# top_blank.net
KiCad netlist of a schematic drawn in Altium Designer
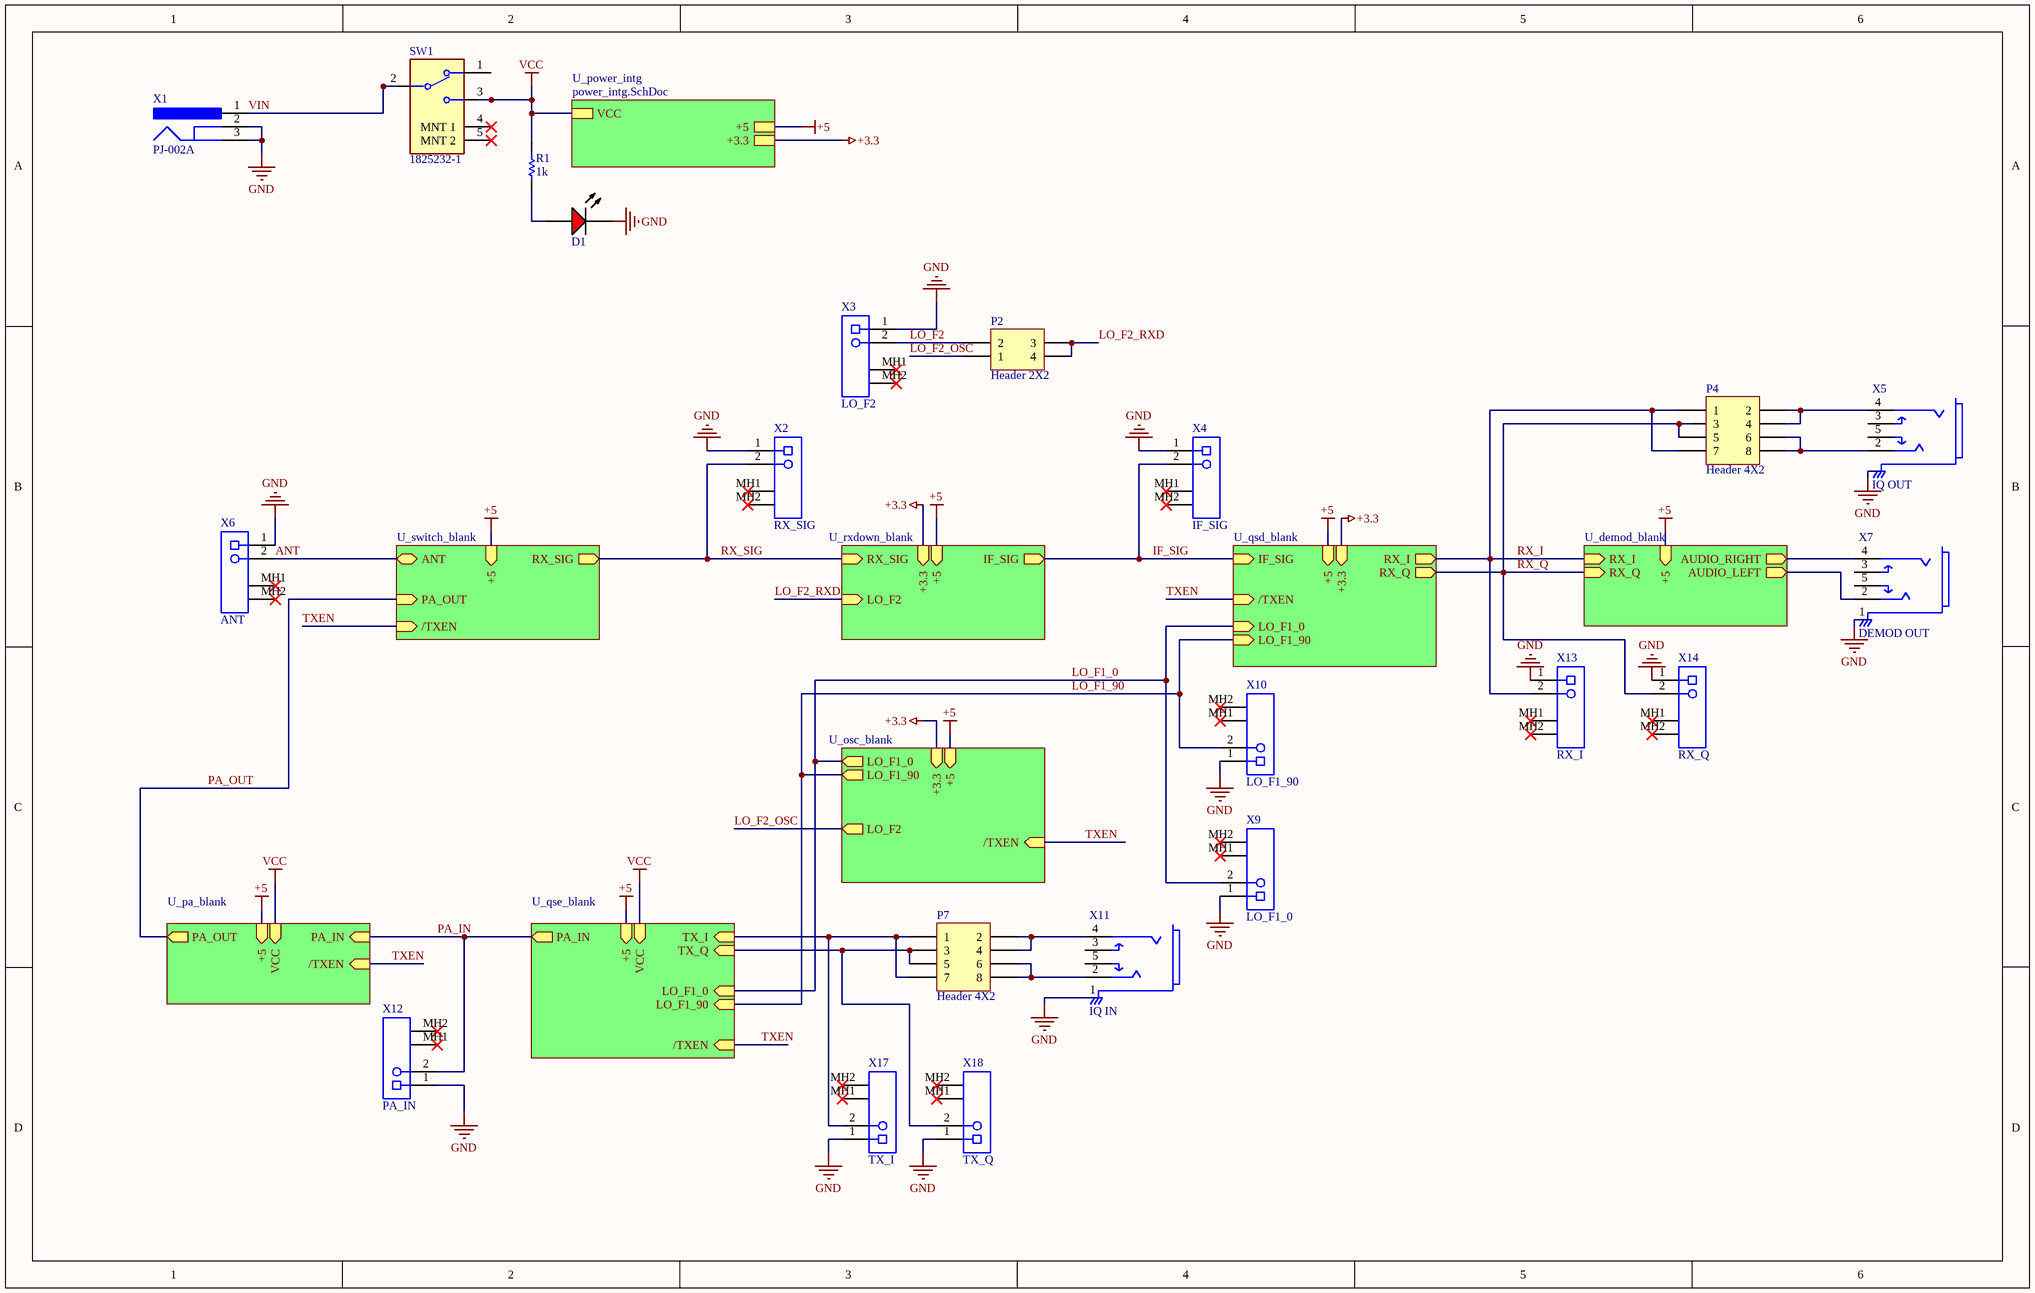
[diagram p0: top_blank.SchDoc]

(export (version "E")
  (design (tool "Eeschema 10.0.6"))
  (components
    (comp (ref "D1")
      (value "HLMP-3301")
      (footprint "AVAG-HLMP-3301-2")
      (description "T-1 3/4 (5 mm) Diffused LED Lamp, 1.9 V, -40 to 100 degC, 2-Pin THD, RoHS, Bulk")
      (fields (field (name "MANUFACTURER") "Avago"))
      (libsource (lib "Altium Content Vault") (part "LED-RED-K1A2-2"))
    )
    (comp (ref "P2")
      (value "Header 2X2")
      (footprint "HDR2X2")
      (description "Header, 2-Pin, Dual row")
      (fields (field (name "PUBLISHER") "Altium Limited"))
      (libsource (lib "Miscellaneous Connectors") (part "Header 2X2"))
    )
    (comp (ref "P4")
      (value "Header 4X2")
      (footprint "HDR2X4")
      (description "Header, 4-Pin, Dual row")
      (fields (field (name "PUBLISHER") "Altium Limited"))
      (libsource (lib "Miscellaneous Connectors") (part "Header 4X2"))
    )
    (comp (ref "P7")
      (value "Header 4X2")
      (footprint "HDR2X4")
      (description "Header, 4-Pin, Dual row")
      (fields (field (name "PUBLISHER") "Altium Limited"))
      (libsource (lib "Miscellaneous Connectors") (part "Header 4X2"))
    )
    (comp (ref "R1")
      (value "1k")
      (footprint "AXIAL-0.4")
      (description "Resistor")
      (fields (field (name "Comment") "Res1") (field (name "PUBLISHER") "Altium Limited"))
      (libsource (lib "Miscellaneous Devices") (part "Res1"))
    )
    (comp (ref "SW1")
      (value "1825232-1")
      (footprint "FP-1825232-1-MFG")
      (description "SWITCH SLIDE SPDT 200MA 30V")
      (fields
        (field (name "OCTOPART") "https://octopart.com/1825232-1-te+connectivity-45209882")
        (field (name "MANUFACTURER") "TE Connectivity")
      )
      (libsource (lib "Altium Content Vault") (part "b81b21e7de6c425a317152e587b8097"))
    )
    (comp (ref "X1")
      (value "PJ-002A")
      (footprint "CUI-PJ-002A_V")
      (fields (field (name "MANUFACTURER") "CUIInc."))
      (libsource (lib "Altium Content Vault") (part "JACK-2CD3-RN"))
    )
    (comp (ref "X2")
      (value "RX_SIG")
      (footprint "TECO-1-1337543-0_V")
      (fields (field (name "MANUFACTURER") "TE Connectivity"))
      (libsource (lib "Altium Content Vault") (part "CN-1P-F-R2_A"))
    )
    (comp (ref "X3")
      (value "LO_F2")
      (footprint "TECO-1-1337543-0_V")
      (fields (field (name "MANUFACTURER") "TE Connectivity"))
      (libsource (lib "") (part "CN-1P-F-R2_A_2"))
    )
    (comp (ref "X4")
      (value "IF_SIG")
      (footprint "TECO-1-1337543-0_V")
      (fields (field (name "MANUFACTURER") "TE Connectivity"))
      (libsource (lib "Altium Content Vault") (part "CN-1P-F-R2_A"))
    )
    (comp (ref "X5")
      (value "IQ OUT")
      (footprint "FP-35RAPC4BV4-MFG")
      (description "CONN JACK STEREO 3.5MM R/A")
      (fields (field (name "MANUFACTURER") "Switchcraft") (field (name "OBSOLETE PART") "true"))
      (libsource (lib "Altium Content Vault") (part "75ff47c9dea01840d0d9527457fc737"))
    )
    (comp (ref "X6")
      (value "ANT")
      (footprint "TECO-1-1337543-0_V")
      (fields (field (name "MANUFACTURER") "TE Connectivity"))
      (libsource (lib "") (part "CN-1P-F-R2_A_2"))
    )
    (comp (ref "X7")
      (value "DEMOD OUT")
      (footprint "FP-35RAPC4BV4-MFG")
      (description "CONN JACK STEREO 3.5MM R/A")
      (fields (field (name "MANUFACTURER") "Switchcraft") (field (name "OBSOLETE PART") "true"))
      (libsource (lib "Altium Content Vault") (part "75ff47c9dea01840d0d9527457fc737"))
    )
    (comp (ref "X9")
      (value "LO_F1_0")
      (footprint "TECO-1-1337543-0_V")
      (fields (field (name "MANUFACTURER") "TE Connectivity"))
      (libsource (lib "") (part "CN-1P-F-R2_A_1"))
    )
    (comp (ref "X10")
      (value "LO_F1_90")
      (footprint "TECO-1-1337543-0_V")
      (fields (field (name "MANUFACTURER") "TE Connectivity"))
      (libsource (lib "") (part "CN-1P-F-R2_A_1"))
    )
    (comp (ref "X11")
      (value "IQ IN")
      (footprint "FP-35RAPC4BV4-MFG")
      (description "CONN JACK STEREO 3.5MM R/A")
      (fields (field (name "MANUFACTURER") "Switchcraft") (field (name "OBSOLETE PART") "true"))
      (libsource (lib "Altium Content Vault") (part "75ff47c9dea01840d0d9527457fc737"))
    )
    (comp (ref "X12")
      (value "PA_IN")
      (footprint "TECO-1-1337543-0_V")
      (fields (field (name "MANUFACTURER") "TE Connectivity"))
      (libsource (lib "") (part "CN-1P-F-R2_A_3"))
    )
    (comp (ref "X13")
      (value "RX_I")
      (footprint "TECO-1-1337543-0_V")
      (fields (field (name "MANUFACTURER") "TE Connectivity"))
      (libsource (lib "Altium Content Vault") (part "CN-1P-F-R2_A"))
    )
    (comp (ref "X14")
      (value "RX_Q")
      (footprint "TECO-1-1337543-0_V")
      (fields (field (name "MANUFACTURER") "TE Connectivity"))
      (libsource (lib "Altium Content Vault") (part "CN-1P-F-R2_A"))
    )
    (comp (ref "X17")
      (value "TX_I")
      (footprint "TECO-1-1337543-0_V")
      (fields (field (name "MANUFACTURER") "TE Connectivity"))
      (libsource (lib "") (part "CN-1P-F-R2_A_1"))
    )
    (comp (ref "X18")
      (value "TX_Q")
      (footprint "TECO-1-1337543-0_V")
      (fields (field (name "MANUFACTURER") "TE Connectivity"))
      (libsource (lib "") (part "CN-1P-F-R2_A_1"))
    )
  )
  (nets
    (net (code "3") (name "/ANT") (class "Default")
      (node (ref "X6") (pin "2") (pinfunction "2_2") (pintype "passive"))
    )
    (net (code "4") (name "/AUDIO_LEFT") (class "Default")
      (node (ref "X7") (pin "2") (pinfunction "2_2") (pintype "passive"))
    )
    (net (code "5") (name "/AUDIO_RIGHT") (class "Default")
      (node (ref "X7") (pin "4") (pinfunction "4_4") (pintype "passive"))
    )
    (net (code "6") (name "/IF_SIG") (class "Default")
      (node (ref "X4") (pin "2") (pinfunction "2_2") (pintype "passive"))
    )
    (net (code "7") (name "/LO_F1_0") (class "Default")
      (node (ref "X9") (pin "2") (pinfunction "2_2") (pintype "passive"))
    )
    (net (code "8") (name "/LO_F1_90") (class "Default")
      (node (ref "X10") (pin "2") (pinfunction "2_2") (pintype "passive"))
    )
    (net (code "9") (name "/LO_F2") (class "Default")
      (node (ref "P2") (pin "2") (pinfunction "2_2") (pintype "passive"))
      (node (ref "X3") (pin "2") (pinfunction "2_2") (pintype "passive"))
    )
    (net (code "10") (name "/LO_F2_OSC") (class "Default")
      (node (ref "P2") (pin "1") (pinfunction "1_1") (pintype "passive"))
    )
    (net (code "11") (name "/LO_F2_RXD") (class "Default")
      (node (ref "P2") (pin "3") (pinfunction "3_3") (pintype "passive"))
      (node (ref "P2") (pin "4") (pinfunction "4_4") (pintype "passive"))
    )
    (net (code "12") (name "/PA_IN") (class "Default")
      (node (ref "X12") (pin "2") (pinfunction "2_2") (pintype "passive"))
    )
    (net (code "14") (name "/RX_I") (class "Default")
      (node (ref "P4") (pin "1") (pinfunction "1_1") (pintype "passive"))
      (node (ref "P4") (pin "7") (pinfunction "7_7") (pintype "passive"))
      (node (ref "X13") (pin "2") (pinfunction "2_2") (pintype "passive"))
    )
    (net (code "15") (name "/RX_Q") (class "Default")
      (node (ref "P4") (pin "3") (pinfunction "3_3") (pintype "passive"))
      (node (ref "P4") (pin "5") (pinfunction "5_5") (pintype "passive"))
      (node (ref "X14") (pin "2") (pinfunction "2_2") (pintype "passive"))
    )
    (net (code "16") (name "/RX_SIG") (class "Default")
      (node (ref "X2") (pin "2") (pinfunction "2_2") (pintype "passive"))
    )
    (net (code "18") (name "/TX_I") (class "Default")
      (node (ref "P7") (pin "1") (pinfunction "1_1") (pintype "passive"))
      (node (ref "P7") (pin "7") (pinfunction "7_7") (pintype "passive"))
      (node (ref "X17") (pin "2") (pinfunction "2_2") (pintype "passive"))
    )
    (net (code "19") (name "/TX_Q") (class "Default")
      (node (ref "P7") (pin "3") (pinfunction "3_3") (pintype "passive"))
      (node (ref "P7") (pin "5") (pinfunction "5_5") (pintype "passive"))
      (node (ref "X18") (pin "2") (pinfunction "2_2") (pintype "passive"))
    )
    (net (code "20") (name "/VIN") (class "Default")
      (node (ref "SW1") (pin "2") (pinfunction "2_2") (pintype "passive"))
      (node (ref "X1") (pin "1") (pinfunction "1_1") (pintype "passive"))
    )
    (net (code "21") (name "GND") (class "Default")
      (node (ref "D1") (pin "1") (pinfunction "K_1") (pintype "passive"))
      (node (ref "X1") (pin "2") (pinfunction "2_2") (pintype "passive"))
      (node (ref "X1") (pin "3") (pinfunction "3_3") (pintype "passive"))
      (node (ref "X10") (pin "1") (pinfunction "1_1") (pintype "passive"))
      (node (ref "X11") (pin "1") (pinfunction "1_1") (pintype "passive"))
      (node (ref "X12") (pin "1") (pinfunction "1_1") (pintype "passive"))
      (node (ref "X13") (pin "1") (pinfunction "1_1") (pintype "passive"))
      (node (ref "X14") (pin "1") (pinfunction "1_1") (pintype "passive"))
      (node (ref "X17") (pin "1") (pinfunction "1_1") (pintype "passive"))
      (node (ref "X18") (pin "1") (pinfunction "1_1") (pintype "passive"))
      (node (ref "X2") (pin "1") (pinfunction "1_1") (pintype "passive"))
      (node (ref "X3") (pin "1") (pinfunction "1_1") (pintype "passive"))
      (node (ref "X4") (pin "1") (pinfunction "1_1") (pintype "passive"))
      (node (ref "X5") (pin "1") (pinfunction "1_1") (pintype "passive"))
      (node (ref "X6") (pin "1") (pinfunction "1_1") (pintype "passive"))
      (node (ref "X7") (pin "1") (pinfunction "1_1") (pintype "passive"))
      (node (ref "X9") (pin "1") (pinfunction "1_1") (pintype "passive"))
    )
    (net (code "22") (name "Net-(D1-A)") (class "Default")
      (node (ref "D1") (pin "2") (pinfunction "A_2") (pintype "passive"))
      (node (ref "R1") (pin "1") (pinfunction "1_1") (pintype "passive"))
    )
    (net (code "23") (name "Net-(P4-Pad2)") (class "Default")
      (node (ref "P4") (pin "2") (pinfunction "2_2") (pintype "passive"))
      (node (ref "P4") (pin "4") (pinfunction "4_4") (pintype "passive"))
      (node (ref "X5") (pin "4") (pinfunction "4_4") (pintype "passive"))
    )
    (net (code "24") (name "Net-(P4-Pad6)") (class "Default")
      (node (ref "P4") (pin "6") (pinfunction "6_6") (pintype "passive"))
      (node (ref "P4") (pin "8") (pinfunction "8_8") (pintype "passive"))
      (node (ref "X5") (pin "2") (pinfunction "2_2") (pintype "passive"))
    )
    (net (code "25") (name "Net-(P7-Pad2)") (class "Default")
      (node (ref "P7") (pin "2") (pinfunction "2_2") (pintype "passive"))
      (node (ref "P7") (pin "4") (pinfunction "4_4") (pintype "passive"))
      (node (ref "X11") (pin "4") (pinfunction "4_4") (pintype "passive"))
    )
    (net (code "26") (name "Net-(P7-Pad6)") (class "Default")
      (node (ref "P7") (pin "6") (pinfunction "6_6") (pintype "passive"))
      (node (ref "P7") (pin "8") (pinfunction "8_8") (pintype "passive"))
      (node (ref "X11") (pin "2") (pinfunction "2_2") (pintype "passive"))
    )
    (net (code "27") (name "VCC") (class "Default")
      (node (ref "R1") (pin "2") (pinfunction "2_2") (pintype "passive"))
      (node (ref "SW1") (pin "3") (pinfunction "3_3") (pintype "passive"))
    )
    (net (code "28") (name "unconnected-(SW1-MNT_1-Pad4)") (class "Default")
      (node (ref "SW1") (pin "4") (pinfunction "MNT_1_4") (pintype "passive+no_connect"))
    )
    (net (code "29") (name "unconnected-(SW1-MNT_2-Pad5)") (class "Default")
      (node (ref "SW1") (pin "5") (pinfunction "MNT_2_5") (pintype "passive+no_connect"))
    )
    (net (code "30") (name "unconnected-(SW1-Pad1)") (class "Default")
      (node (ref "SW1") (pin "1") (pinfunction "1_1") (pintype "passive"))
    )
    (net (code "31") (name "unconnected-(X2-PadMH1)") (class "Default")
      (node (ref "X2") (pin "MH1") (pinfunction "MH1_MH1") (pintype "passive+no_connect"))
    )
    (net (code "32") (name "unconnected-(X2-PadMH2)") (class "Default")
      (node (ref "X2") (pin "MH2") (pinfunction "MH2_MH2") (pintype "passive+no_connect"))
    )
    (net (code "33") (name "unconnected-(X3-PadMH1)") (class "Default")
      (node (ref "X3") (pin "MH1") (pinfunction "MH1_MH1") (pintype "passive+no_connect"))
    )
    (net (code "34") (name "unconnected-(X3-PadMH2)") (class "Default")
      (node (ref "X3") (pin "MH2") (pinfunction "MH2_MH2") (pintype "passive+no_connect"))
    )
    (net (code "35") (name "unconnected-(X4-PadMH1)") (class "Default")
      (node (ref "X4") (pin "MH1") (pinfunction "MH1_MH1") (pintype "passive+no_connect"))
    )
    (net (code "36") (name "unconnected-(X4-PadMH2)") (class "Default")
      (node (ref "X4") (pin "MH2") (pinfunction "MH2_MH2") (pintype "passive+no_connect"))
    )
    (net (code "37") (name "unconnected-(X5-Pad3)") (class "Default")
      (node (ref "X5") (pin "3") (pinfunction "3_3") (pintype "passive"))
    )
    (net (code "38") (name "unconnected-(X5-Pad5)") (class "Default")
      (node (ref "X5") (pin "5") (pinfunction "5_5") (pintype "passive"))
    )
    (net (code "39") (name "unconnected-(X6-PadMH1)") (class "Default")
      (node (ref "X6") (pin "MH1") (pinfunction "MH1_MH1") (pintype "passive+no_connect"))
    )
    (net (code "40") (name "unconnected-(X6-PadMH2)") (class "Default")
      (node (ref "X6") (pin "MH2") (pinfunction "MH2_MH2") (pintype "passive+no_connect"))
    )
    (net (code "41") (name "unconnected-(X7-Pad3)") (class "Default")
      (node (ref "X7") (pin "3") (pinfunction "3_3") (pintype "passive"))
    )
    (net (code "42") (name "unconnected-(X7-Pad5)") (class "Default")
      (node (ref "X7") (pin "5") (pinfunction "5_5") (pintype "passive"))
    )
    (net (code "43") (name "unconnected-(X9-PadMH1)") (class "Default")
      (node (ref "X9") (pin "MH1") (pinfunction "MH1_MH1") (pintype "passive+no_connect"))
    )
    (net (code "44") (name "unconnected-(X9-PadMH2)") (class "Default")
      (node (ref "X9") (pin "MH2") (pinfunction "MH2_MH2") (pintype "passive+no_connect"))
    )
    (net (code "45") (name "unconnected-(X10-PadMH1)") (class "Default")
      (node (ref "X10") (pin "MH1") (pinfunction "MH1_MH1") (pintype "passive+no_connect"))
    )
    (net (code "46") (name "unconnected-(X10-PadMH2)") (class "Default")
      (node (ref "X10") (pin "MH2") (pinfunction "MH2_MH2") (pintype "passive+no_connect"))
    )
    (net (code "47") (name "unconnected-(X11-Pad3)") (class "Default")
      (node (ref "X11") (pin "3") (pinfunction "3_3") (pintype "passive"))
    )
    (net (code "48") (name "unconnected-(X11-Pad5)") (class "Default")
      (node (ref "X11") (pin "5") (pinfunction "5_5") (pintype "passive"))
    )
    (net (code "49") (name "unconnected-(X12-PadMH1)") (class "Default")
      (node (ref "X12") (pin "MH1") (pinfunction "MH1_MH1") (pintype "passive+no_connect"))
    )
    (net (code "50") (name "unconnected-(X12-PadMH2)") (class "Default")
      (node (ref "X12") (pin "MH2") (pinfunction "MH2_MH2") (pintype "passive+no_connect"))
    )
    (net (code "51") (name "unconnected-(X13-PadMH1)") (class "Default")
      (node (ref "X13") (pin "MH1") (pinfunction "MH1_MH1") (pintype "passive+no_connect"))
    )
    (net (code "52") (name "unconnected-(X13-PadMH2)") (class "Default")
      (node (ref "X13") (pin "MH2") (pinfunction "MH2_MH2") (pintype "passive+no_connect"))
    )
    (net (code "53") (name "unconnected-(X14-PadMH1)") (class "Default")
      (node (ref "X14") (pin "MH1") (pinfunction "MH1_MH1") (pintype "passive+no_connect"))
    )
    (net (code "54") (name "unconnected-(X14-PadMH2)") (class "Default")
      (node (ref "X14") (pin "MH2") (pinfunction "MH2_MH2") (pintype "passive+no_connect"))
    )
    (net (code "55") (name "unconnected-(X17-PadMH1)") (class "Default")
      (node (ref "X17") (pin "MH1") (pinfunction "MH1_MH1") (pintype "passive+no_connect"))
    )
    (net (code "56") (name "unconnected-(X17-PadMH2)") (class "Default")
      (node (ref "X17") (pin "MH2") (pinfunction "MH2_MH2") (pintype "passive+no_connect"))
    )
    (net (code "57") (name "unconnected-(X18-PadMH1)") (class "Default")
      (node (ref "X18") (pin "MH1") (pinfunction "MH1_MH1") (pintype "passive+no_connect"))
    )
    (net (code "58") (name "unconnected-(X18-PadMH2)") (class "Default")
      (node (ref "X18") (pin "MH2") (pinfunction "MH2_MH2") (pintype "passive+no_connect"))
    )
  )
)
